# 9x_Connection_Board_B_v0_3.net
KiCad netlist of a schematic drawn in EAGLE
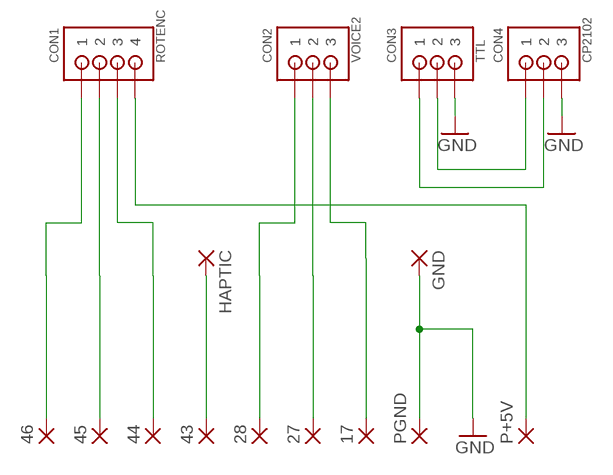
[diagram p0: schematic, sheet 1]

(export (version "E")
  (design (tool "Eeschema 10.0.6"))
  (components
    (comp (ref "17")
      (value "WIREPADSMD1,27-254")
      (footprint "eagle-import:SMD1,27-2,54")
      (libsource (lib "eagle-import") (part "WIREPADSMD1,27-254"))
    )
    (comp (ref "27")
      (value "WIREPADSMD1,27-254")
      (footprint "eagle-import:SMD1,27-2,54")
      (libsource (lib "eagle-import") (part "WIREPADSMD1,27-254"))
    )
    (comp (ref "28")
      (value "WIREPADSMD1,27-254")
      (footprint "eagle-import:SMD1,27-2,54")
      (libsource (lib "eagle-import") (part "WIREPADSMD1,27-254"))
    )
    (comp (ref "43")
      (value "WIREPADSMD1,27-254")
      (footprint "eagle-import:SMD1,27-2,54")
      (libsource (lib "eagle-import") (part "WIREPADSMD1,27-254"))
    )
    (comp (ref "44")
      (value "WIREPADSMD1,27-254")
      (footprint "eagle-import:SMD1,27-2,54")
      (libsource (lib "eagle-import") (part "WIREPADSMD1,27-254"))
    )
    (comp (ref "45")
      (value "WIREPADSMD1,27-254")
      (footprint "eagle-import:SMD1,27-2,54")
      (libsource (lib "eagle-import") (part "WIREPADSMD1,27-254"))
    )
    (comp (ref "46")
      (value "WIREPADSMD1,27-254")
      (footprint "eagle-import:SMD1,27-2,54")
      (libsource (lib "eagle-import") (part "WIREPADSMD1,27-254"))
    )
    (comp (ref "CON1")
      (value "ROTENC")
      (footprint "eagle-import:B4B-ZR")
      (libsource (lib "eagle-import") (part "B4B-ZR"))
    )
    (comp (ref "CON2")
      (value "VOICE2")
      (footprint "eagle-import:B3B-ZR")
      (libsource (lib "eagle-import") (part "B3B-ZR"))
    )
    (comp (ref "CON3")
      (value "TTL")
      (footprint "eagle-import:B3B-ZR")
      (libsource (lib "eagle-import") (part "B3B-ZR"))
    )
    (comp (ref "CON4")
      (value "CP2102")
      (footprint "eagle-import:B3B-ZR")
      (libsource (lib "eagle-import") (part "B3B-ZR"))
    )
    (comp (ref "GND")
      (value "WIREPADSMD1,27-254")
      (footprint "eagle-import:SMD1,27-2,54")
      (libsource (lib "eagle-import") (part "WIREPADSMD1,27-254"))
    )
    (comp (ref "HAPTIC")
      (value "WIREPADSMD1,27-254")
      (footprint "eagle-import:SMD1,27-2,54")
      (libsource (lib "eagle-import") (part "WIREPADSMD1,27-254"))
    )
    (comp (ref "P+5V")
      (value "WIREPADSMD1,27-254")
      (footprint "eagle-import:SMD1,27-2,54")
      (libsource (lib "eagle-import") (part "WIREPADSMD1,27-254"))
    )
    (comp (ref "PGND")
      (value "WIREPADSMD1,27-254")
      (footprint "eagle-import:SMD1,27-2,54")
      (libsource (lib "eagle-import") (part "WIREPADSMD1,27-254"))
    )
  )
  (nets
    (net (code "1") (name "GND") (class "Default")
      (node (ref "CON3") (pin "3") (pinfunction "3_3") (pintype "bidirectional"))
      (node (ref "CON4") (pin "3") (pinfunction "3_3") (pintype "bidirectional"))
      (node (ref "GND") (pin "1") (pinfunction "P_1") (pintype "passive"))
      (node (ref "PGND") (pin "1") (pinfunction "P_1") (pintype "passive"))
    )
    (net (code "2") (name "Net-(17-P)") (class "Default")
      (node (ref "17") (pin "1") (pinfunction "P_1") (pintype "passive"))
      (node (ref "CON2") (pin "3") (pinfunction "3_3") (pintype "bidirectional"))
    )
    (net (code "3") (name "Net-(27-P)") (class "Default")
      (node (ref "27") (pin "1") (pinfunction "P_1") (pintype "passive"))
      (node (ref "CON2") (pin "2") (pinfunction "2_2") (pintype "bidirectional"))
    )
    (net (code "4") (name "Net-(28-P)") (class "Default")
      (node (ref "28") (pin "1") (pinfunction "P_1") (pintype "passive"))
      (node (ref "CON2") (pin "1") (pinfunction "1_1") (pintype "bidirectional"))
    )
    (net (code "5") (name "Net-(43-P)") (class "Default")
      (node (ref "43") (pin "1") (pinfunction "P_1") (pintype "passive"))
      (node (ref "HAPTIC") (pin "1") (pinfunction "P_1") (pintype "passive"))
    )
    (net (code "6") (name "Net-(44-P)") (class "Default")
      (node (ref "44") (pin "1") (pinfunction "P_1") (pintype "passive"))
      (node (ref "CON1") (pin "3") (pinfunction "3_3") (pintype "bidirectional"))
    )
    (net (code "7") (name "Net-(45-P)") (class "Default")
      (node (ref "45") (pin "1") (pinfunction "P_1") (pintype "passive"))
      (node (ref "CON1") (pin "2") (pinfunction "2_2") (pintype "bidirectional"))
    )
    (net (code "8") (name "Net-(46-P)") (class "Default")
      (node (ref "46") (pin "1") (pinfunction "P_1") (pintype "passive"))
      (node (ref "CON1") (pin "1") (pinfunction "1_1") (pintype "bidirectional"))
    )
    (net (code "9") (name "Net-(CON3-Pad1)") (class "Default")
      (node (ref "CON3") (pin "1") (pinfunction "1_1") (pintype "bidirectional"))
      (node (ref "CON4") (pin "2") (pinfunction "2_2") (pintype "bidirectional"))
    )
    (net (code "10") (name "Net-(CON3-Pad2)") (class "Default")
      (node (ref "CON3") (pin "2") (pinfunction "2_2") (pintype "bidirectional"))
      (node (ref "CON4") (pin "1") (pinfunction "1_1") (pintype "bidirectional"))
    )
    (net (code "11") (name "Net-(P+5V-P)") (class "Default")
      (node (ref "CON1") (pin "4") (pinfunction "4_4") (pintype "bidirectional"))
      (node (ref "P+5V") (pin "1") (pinfunction "P_1") (pintype "passive"))
    )
  )
)
